# kostka.net
KiCad netlist of a schematic drawn in EAGLE
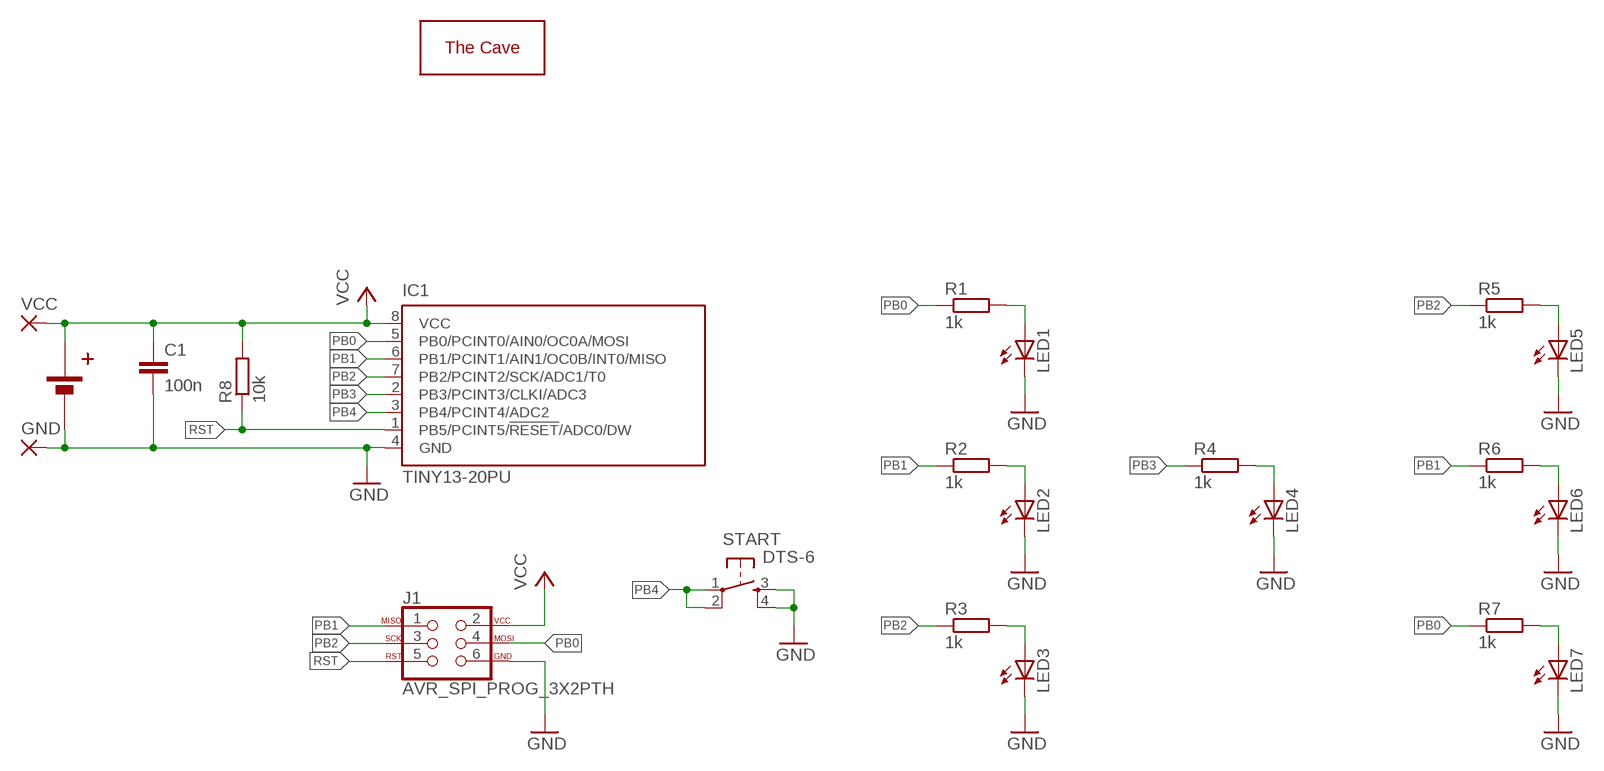
[diagram p0: schematic, sheet 1]

(export (version "E")
  (design (tool "Eeschema 10.0.6"))
  (components
    (comp (ref "C1")
      (value "100n")
      (footprint "eagle-import:C025-025X050")
      (libsource (lib "eagle-import") (part "C-EU025-025X050"))
    )
    (comp (ref "GND")
      (value "WIREPADSMD1,27-254")
      (footprint "eagle-import:SMD1,27-2,54")
      (libsource (lib "eagle-import") (part "WIREPADSMD1,27-254"))
    )
    (comp (ref "IC1")
      (value "TINY13-20PU")
      (footprint "eagle-import:DIL08")
      (fields (field (name "MPN") "ATTINY13-20PU"))
      (libsource (lib "eagle-import") (part "TINY13PU-20"))
    )
    (comp (ref "J1")
      (value "AVR_SPI_PROG_3X2PTH")
      (footprint "eagle-import:2X3")
      (libsource (lib "eagle-import") (part "AVR_SPI_PROG_3X2PTH"))
    )
    (comp (ref "LED1")
      (value "LED5MM")
      (footprint "eagle-import:LED5MM")
      (libsource (lib "eagle-import") (part "LED5MM"))
    )
    (comp (ref "LED2")
      (value "LED5MM")
      (footprint "eagle-import:LED5MM")
      (libsource (lib "eagle-import") (part "LED5MM"))
    )
    (comp (ref "LED3")
      (value "LED5MM")
      (footprint "eagle-import:LED5MM")
      (libsource (lib "eagle-import") (part "LED5MM"))
    )
    (comp (ref "LED4")
      (value "LED5MM")
      (footprint "eagle-import:LED5MM")
      (libsource (lib "eagle-import") (part "LED5MM"))
    )
    (comp (ref "LED5")
      (value "LED5MM")
      (footprint "eagle-import:LED5MM")
      (libsource (lib "eagle-import") (part "LED5MM"))
    )
    (comp (ref "LED6")
      (value "LED5MM")
      (footprint "eagle-import:LED5MM")
      (libsource (lib "eagle-import") (part "LED5MM"))
    )
    (comp (ref "LED7")
      (value "LED5MM")
      (footprint "eagle-import:LED5MM")
      (libsource (lib "eagle-import") (part "LED5MM"))
    )
    (comp (ref "R1")
      (value "1k")
      (footprint "eagle-import:0207_7")
      (libsource (lib "eagle-import") (part "R-EU_0207/7"))
    )
    (comp (ref "R2")
      (value "1k")
      (footprint "eagle-import:0207_7")
      (libsource (lib "eagle-import") (part "R-EU_0207/7"))
    )
    (comp (ref "R3")
      (value "1k")
      (footprint "eagle-import:0207_7")
      (libsource (lib "eagle-import") (part "R-EU_0207/7"))
    )
    (comp (ref "R4")
      (value "1k")
      (footprint "eagle-import:0207_7")
      (libsource (lib "eagle-import") (part "R-EU_0207/7"))
    )
    (comp (ref "R5")
      (value "1k")
      (footprint "eagle-import:0207_7")
      (libsource (lib "eagle-import") (part "R-EU_0207/7"))
    )
    (comp (ref "R6")
      (value "1k")
      (footprint "eagle-import:0207_7")
      (libsource (lib "eagle-import") (part "R-EU_0207/7"))
    )
    (comp (ref "R7")
      (value "1k")
      (footprint "eagle-import:0207_7")
      (libsource (lib "eagle-import") (part "R-EU_0207/7"))
    )
    (comp (ref "R8")
      (value "10k")
      (footprint "eagle-import:0207_7")
      (libsource (lib "eagle-import") (part "R-EU_0207/7"))
    )
    (comp (ref "START")
      (value "DTS-6")
      (footprint "eagle-import:DTS-6")
      (libsource (lib "eagle-import") (part "DTS-6"))
    )
    (comp (ref "U$1")
      (value "THECAVE_LOGO_NEW_BOTTOM")
      (footprint "eagle-import:NEW_LOGO_BOTTOM")
      (libsource (lib "eagle-import") (part "THECAVE_LOGO_NEW_BOTTOM"))
    )
    (comp (ref "VCC")
      (value "WIREPADSMD1,27-254")
      (footprint "eagle-import:SMD1,27-2,54")
      (libsource (lib "eagle-import") (part "WIREPADSMD1,27-254"))
    )
    (comp (ref "X1")
      (value "CR2032H_HOLD2")
      (footprint "eagle-import:CR2032HZ")
      (libsource (lib "eagle-import") (part "CR2032H_HOLD2"))
    )
  )
  (nets
    (net (code "1") (name "GND") (class "Default")
      (node (ref "C1") (pin "2") (pinfunction "2_2") (pintype "passive"))
      (node (ref "GND") (pin "1") (pinfunction "P_1") (pintype "passive"))
      (node (ref "IC1") (pin "4") (pinfunction "GND_4") (pintype "power_in"))
      (node (ref "J1") (pin "6") (pinfunction "6_6") (pintype "passive"))
      (node (ref "LED1") (pin "K") (pinfunction "C_K") (pintype "passive"))
      (node (ref "LED2") (pin "K") (pinfunction "C_K") (pintype "passive"))
      (node (ref "LED3") (pin "K") (pinfunction "C_K") (pintype "passive"))
      (node (ref "LED4") (pin "K") (pinfunction "C_K") (pintype "passive"))
      (node (ref "LED5") (pin "K") (pinfunction "C_K") (pintype "passive"))
      (node (ref "LED6") (pin "K") (pinfunction "C_K") (pintype "passive"))
      (node (ref "LED7") (pin "K") (pinfunction "C_K") (pintype "passive"))
      (node (ref "START") (pin "3") (pinfunction "3_3") (pintype "passive"))
      (node (ref "START") (pin "4") (pinfunction "4_4") (pintype "passive"))
      (node (ref "X1") (pin "MINUS") (pinfunction "GND_MINUS") (pintype "power_in"))
    )
    (net (code "2") (name "Net-(LED1-PadA)") (class "Default")
      (node (ref "LED1") (pin "A") (pinfunction "A_A") (pintype "passive"))
      (node (ref "R1") (pin "2") (pinfunction "2_2") (pintype "passive"))
    )
    (net (code "3") (name "Net-(LED2-PadA)") (class "Default")
      (node (ref "LED2") (pin "A") (pinfunction "A_A") (pintype "passive"))
      (node (ref "R2") (pin "2") (pinfunction "2_2") (pintype "passive"))
    )
    (net (code "4") (name "Net-(LED3-PadA)") (class "Default")
      (node (ref "LED3") (pin "A") (pinfunction "A_A") (pintype "passive"))
      (node (ref "R3") (pin "2") (pinfunction "2_2") (pintype "passive"))
    )
    (net (code "5") (name "Net-(LED4-PadA)") (class "Default")
      (node (ref "LED4") (pin "A") (pinfunction "A_A") (pintype "passive"))
      (node (ref "R4") (pin "2") (pinfunction "2_2") (pintype "passive"))
    )
    (net (code "6") (name "Net-(LED5-PadA)") (class "Default")
      (node (ref "LED5") (pin "A") (pinfunction "A_A") (pintype "passive"))
      (node (ref "R5") (pin "2") (pinfunction "2_2") (pintype "passive"))
    )
    (net (code "7") (name "Net-(LED6-PadA)") (class "Default")
      (node (ref "LED6") (pin "A") (pinfunction "A_A") (pintype "passive"))
      (node (ref "R6") (pin "2") (pinfunction "2_2") (pintype "passive"))
    )
    (net (code "8") (name "Net-(LED7-PadA)") (class "Default")
      (node (ref "LED7") (pin "A") (pinfunction "A_A") (pintype "passive"))
      (node (ref "R7") (pin "2") (pinfunction "2_2") (pintype "passive"))
    )
    (net (code "9") (name "PB0") (class "Default")
      (node (ref "IC1") (pin "5") (pinfunction "PB0/PCINT0/AIN0/OC0A/MOSI_5") (pintype "bidirectional"))
      (node (ref "J1") (pin "4") (pinfunction "4_4") (pintype "passive"))
      (node (ref "R1") (pin "1") (pinfunction "1_1") (pintype "passive"))
      (node (ref "R7") (pin "1") (pinfunction "1_1") (pintype "passive"))
    )
    (net (code "10") (name "PB1") (class "Default")
      (node (ref "IC1") (pin "6") (pinfunction "PB1/PCINT1/AIN1/OC0B/INT0/MISO_6") (pintype "bidirectional"))
      (node (ref "J1") (pin "1") (pinfunction "1_1") (pintype "passive"))
      (node (ref "R2") (pin "1") (pinfunction "1_1") (pintype "passive"))
      (node (ref "R6") (pin "1") (pinfunction "1_1") (pintype "passive"))
    )
    (net (code "11") (name "PB2") (class "Default")
      (node (ref "IC1") (pin "7") (pinfunction "PB2/PCINT2/SCK/ADC1/T0_7") (pintype "bidirectional"))
      (node (ref "J1") (pin "3") (pinfunction "3_3") (pintype "passive"))
      (node (ref "R3") (pin "1") (pinfunction "1_1") (pintype "passive"))
      (node (ref "R5") (pin "1") (pinfunction "1_1") (pintype "passive"))
    )
    (net (code "12") (name "PB3") (class "Default")
      (node (ref "IC1") (pin "2") (pinfunction "PB3/PCINT3/CLKI/ADC3_2") (pintype "bidirectional"))
      (node (ref "R4") (pin "1") (pinfunction "1_1") (pintype "passive"))
    )
    (net (code "13") (name "PB4") (class "Default")
      (node (ref "IC1") (pin "3") (pinfunction "PB4/PCINT4/ADC2_3") (pintype "bidirectional"))
      (node (ref "START") (pin "1") (pinfunction "1_1") (pintype "passive"))
      (node (ref "START") (pin "2") (pinfunction "2_2") (pintype "passive"))
    )
    (net (code "14") (name "RST") (class "Default")
      (node (ref "IC1") (pin "1") (pinfunction "PB5/PCINT5/~{RESET}/ADC0/DW_1") (pintype "bidirectional"))
      (node (ref "J1") (pin "5") (pinfunction "5_5") (pintype "passive"))
      (node (ref "R8") (pin "1") (pinfunction "1_1") (pintype "passive"))
    )
    (net (code "15") (name "VCC") (class "Default")
      (node (ref "C1") (pin "1") (pinfunction "1_1") (pintype "passive"))
      (node (ref "IC1") (pin "8") (pinfunction "VCC_8") (pintype "power_in"))
      (node (ref "J1") (pin "2") (pinfunction "2_2") (pintype "passive"))
      (node (ref "R8") (pin "2") (pinfunction "2_2") (pintype "passive"))
      (node (ref "VCC") (pin "1") (pinfunction "P_1") (pintype "passive"))
      (node (ref "X1") (pin "PLUS") (pinfunction "VCC_PLUS") (pintype "power_in"))
    )
  )
)
